# courtyard_distboard.net
KiCad netlist of a schematic drawn in EAGLE
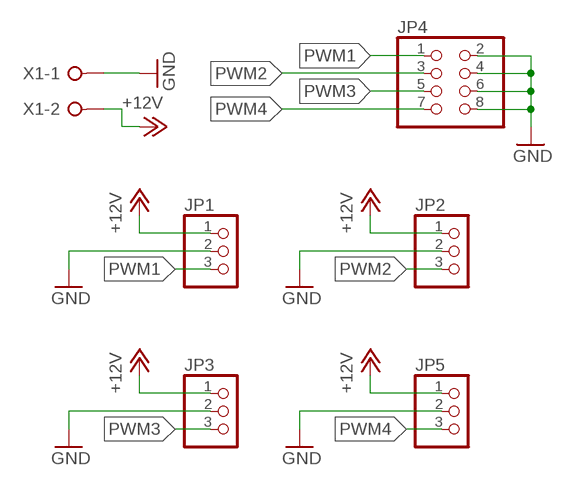
[diagram p0: schematic, sheet 1]

(export (version "E")
  (design (tool "Eeschema 10.0.6"))
  (components
    (comp (ref "JP1")
      (value "PINHD-1X3")
      (footprint "eagle-import:1X03")
      (libsource (lib "eagle-import") (part "PINHD-1X3"))
    )
    (comp (ref "JP2")
      (value "PINHD-1X3")
      (footprint "eagle-import:1X03")
      (libsource (lib "eagle-import") (part "PINHD-1X3"))
    )
    (comp (ref "JP3")
      (value "PINHD-1X3")
      (footprint "eagle-import:1X03")
      (libsource (lib "eagle-import") (part "PINHD-1X3"))
    )
    (comp (ref "JP4")
      (value "PINHD-2X4")
      (footprint "eagle-import:2X04")
      (libsource (lib "eagle-import") (part "PINHD-2X4"))
    )
    (comp (ref "JP5")
      (value "PINHD-1X3")
      (footprint "eagle-import:1X03")
      (libsource (lib "eagle-import") (part "PINHD-1X3"))
    )
    (comp (ref "X1")
      (value "W237-02P")
      (footprint "eagle-import:W237-132")
      (libsource (lib "eagle-import") (part "W237-02P"))
    )
  )
  (nets
    (net (code "1") (name "+12V") (class "Default")
      (node (ref "JP1") (pin "1") (pinfunction "1_1") (pintype "passive"))
      (node (ref "JP2") (pin "1") (pinfunction "1_1") (pintype "passive"))
      (node (ref "JP3") (pin "1") (pinfunction "1_1") (pintype "passive"))
      (node (ref "JP5") (pin "1") (pinfunction "1_1") (pintype "passive"))
      (node (ref "X1") (pin "2") (pinfunction "KL_2") (pintype "passive"))
    )
    (net (code "2") (name "GND") (class "Default")
      (node (ref "JP1") (pin "2") (pinfunction "2_2") (pintype "passive"))
      (node (ref "JP2") (pin "2") (pinfunction "2_2") (pintype "passive"))
      (node (ref "JP3") (pin "2") (pinfunction "2_2") (pintype "passive"))
      (node (ref "JP4") (pin "2") (pinfunction "2_2") (pintype "passive"))
      (node (ref "JP4") (pin "4") (pinfunction "4_4") (pintype "passive"))
      (node (ref "JP4") (pin "6") (pinfunction "6_6") (pintype "passive"))
      (node (ref "JP4") (pin "8") (pinfunction "8_8") (pintype "passive"))
      (node (ref "JP5") (pin "2") (pinfunction "2_2") (pintype "passive"))
      (node (ref "X1") (pin "1") (pinfunction "KL_1") (pintype "passive"))
    )
    (net (code "3") (name "PWM1") (class "Default")
      (node (ref "JP1") (pin "3") (pinfunction "3_3") (pintype "passive"))
      (node (ref "JP4") (pin "1") (pinfunction "1_1") (pintype "passive"))
    )
    (net (code "4") (name "PWM2") (class "Default")
      (node (ref "JP2") (pin "3") (pinfunction "3_3") (pintype "passive"))
      (node (ref "JP4") (pin "3") (pinfunction "3_3") (pintype "passive"))
    )
    (net (code "5") (name "PWM3") (class "Default")
      (node (ref "JP3") (pin "3") (pinfunction "3_3") (pintype "passive"))
      (node (ref "JP4") (pin "5") (pinfunction "5_5") (pintype "passive"))
    )
    (net (code "6") (name "PWM4") (class "Default")
      (node (ref "JP4") (pin "7") (pinfunction "7_7") (pintype "passive"))
      (node (ref "JP5") (pin "3") (pinfunction "3_3") (pintype "passive"))
    )
  )
)
